# matrix.net
KiCad netlist of a schematic drawn in EAGLE
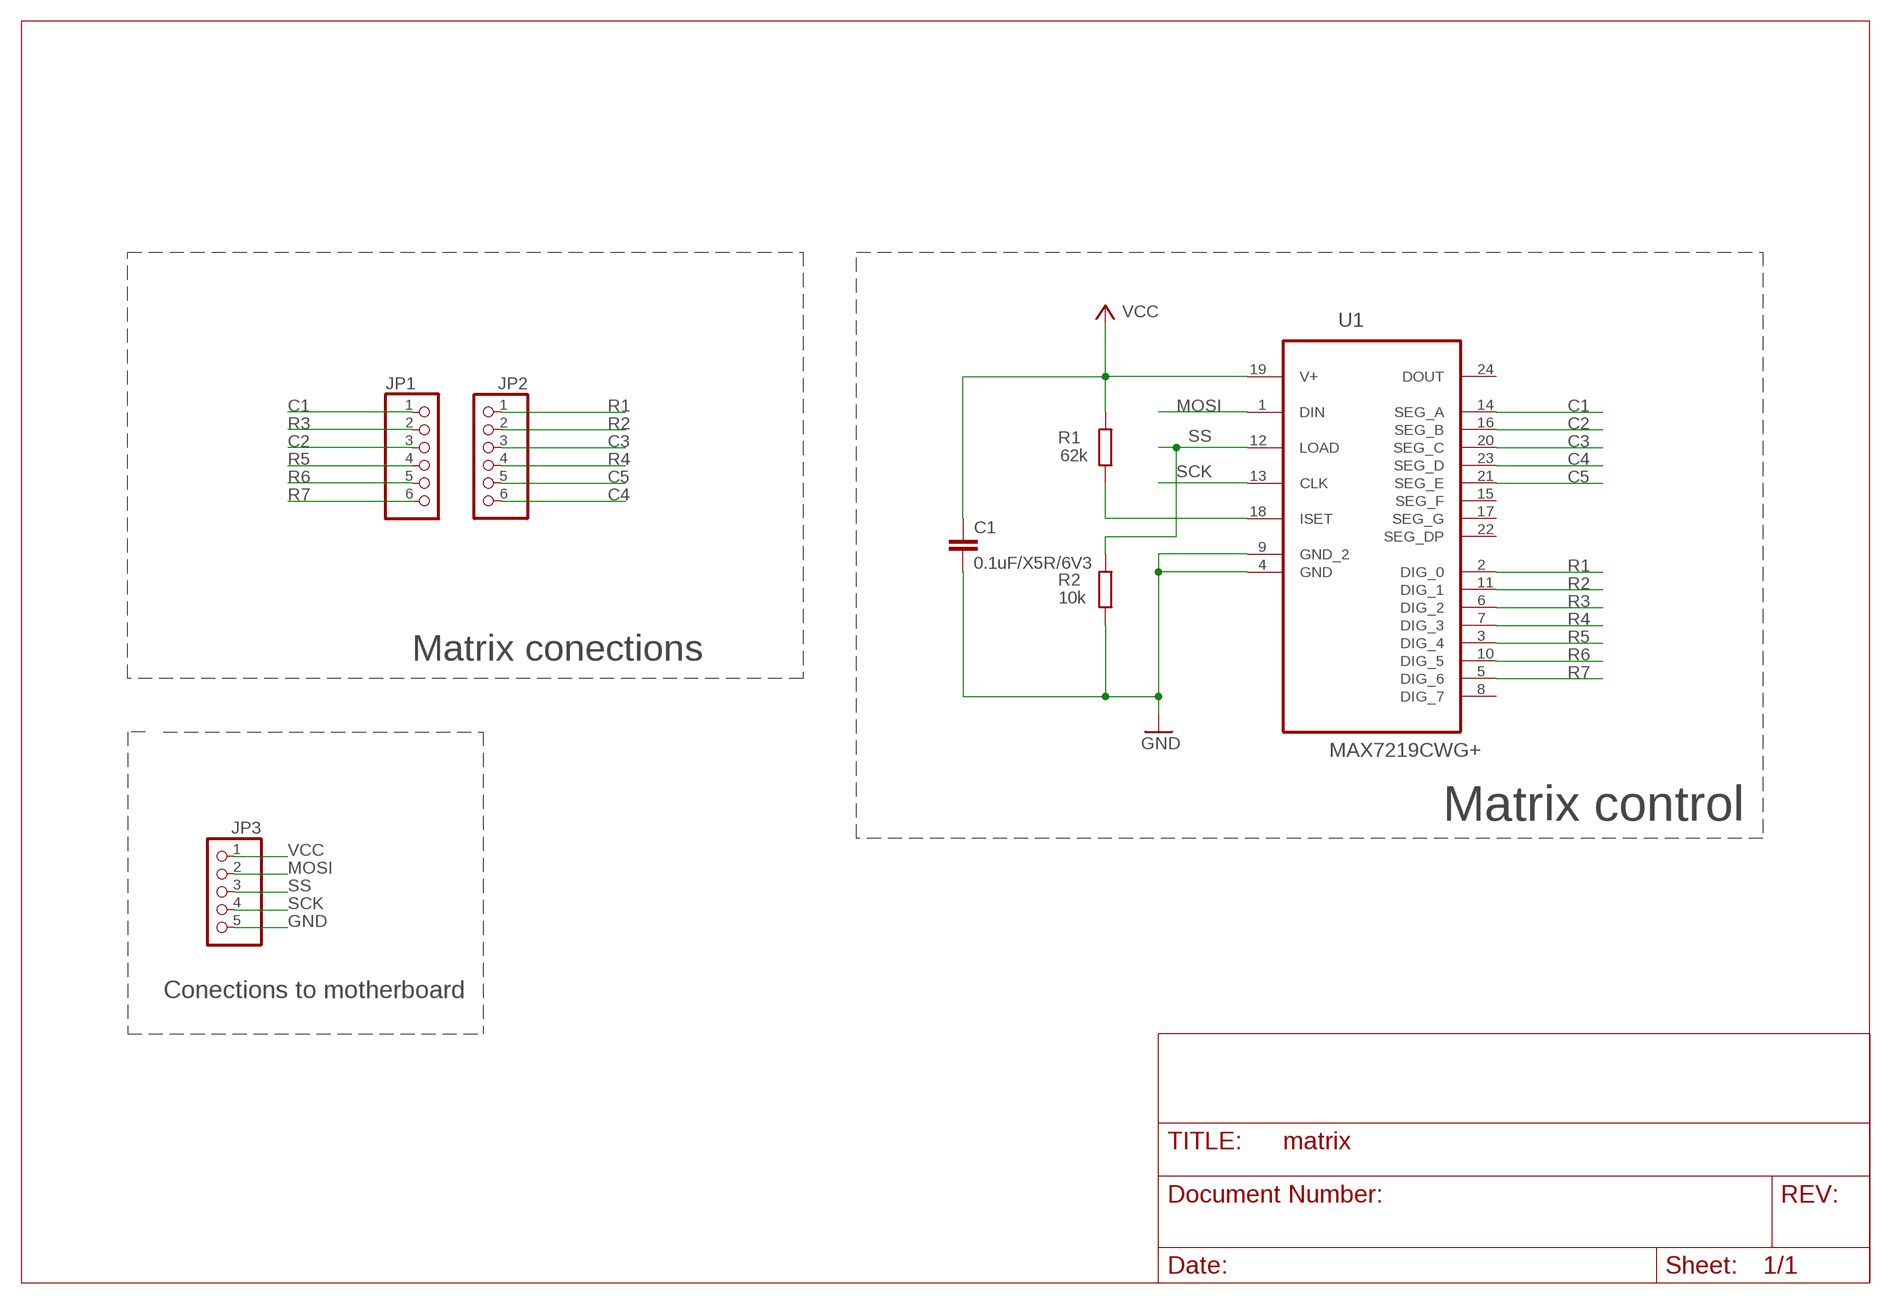
[diagram p0: schematic, sheet 1]

(export (version "E")
  (design (tool "Eeschema 10.0.6"))
  (components
    (comp (ref "C1")
      (value "0.1uF/X5R/6V3")
      (footprint "eagle-import:C1206")
      (libsource (lib "eagle-import") (part "C-EUC1206"))
    )
    (comp (ref "JP1")
      (value "PINHD-1X6")
      (footprint "eagle-import:1X06")
      (libsource (lib "eagle-import") (part "PINHD-1X6"))
    )
    (comp (ref "JP2")
      (value "PINHD-1X6")
      (footprint "eagle-import:1X06")
      (libsource (lib "eagle-import") (part "PINHD-1X6"))
    )
    (comp (ref "JP3")
      (value "PINHD-1X5")
      (footprint "eagle-import:1X05")
      (libsource (lib "eagle-import") (part "PINHD-1X5"))
    )
    (comp (ref "R1")
      (value "62k")
      (footprint "eagle-import:R0805")
      (libsource (lib "eagle-import") (part "R-EU_R0805"))
    )
    (comp (ref "R2")
      (value "10k")
      (footprint "eagle-import:R0805")
      (libsource (lib "eagle-import") (part "R-EU_R0805"))
    )
    (comp (ref "U1")
      (value "MAX7219CWG+")
      (footprint "eagle-import:SOIC127P1032X265-24N")
      (libsource (lib "eagle-import") (part "MAX7219CWG+"))
    )
  )
  (nets
    (net (code "1") (name "/C1") (class "Default")
      (node (ref "JP1") (pin "1") (pinfunction "1_1") (pintype "passive"))
      (node (ref "U1") (pin "14") (pinfunction "SEG_A_14") (pintype "output"))
    )
    (net (code "2") (name "/C2") (class "Default")
      (node (ref "JP1") (pin "3") (pinfunction "3_3") (pintype "passive"))
      (node (ref "U1") (pin "16") (pinfunction "SEG_B_16") (pintype "output"))
    )
    (net (code "3") (name "/C3") (class "Default")
      (node (ref "JP2") (pin "3") (pinfunction "3_3") (pintype "passive"))
      (node (ref "U1") (pin "20") (pinfunction "SEG_C_20") (pintype "output"))
    )
    (net (code "4") (name "/C4") (class "Default")
      (node (ref "JP2") (pin "6") (pinfunction "6_6") (pintype "passive"))
      (node (ref "U1") (pin "23") (pinfunction "SEG_D_23") (pintype "output"))
    )
    (net (code "5") (name "/C5") (class "Default")
      (node (ref "JP2") (pin "5") (pinfunction "5_5") (pintype "passive"))
      (node (ref "U1") (pin "21") (pinfunction "SEG_E_21") (pintype "output"))
    )
    (net (code "6") (name "/MOSI") (class "Default")
      (node (ref "JP3") (pin "2") (pinfunction "2_2") (pintype "passive"))
      (node (ref "U1") (pin "1") (pinfunction "DIN_1") (pintype "input"))
    )
    (net (code "7") (name "/R1") (class "Default")
      (node (ref "JP2") (pin "1") (pinfunction "1_1") (pintype "passive"))
      (node (ref "U1") (pin "2") (pinfunction "DIG_0_2") (pintype "output"))
    )
    (net (code "8") (name "/R2") (class "Default")
      (node (ref "JP2") (pin "2") (pinfunction "2_2") (pintype "passive"))
      (node (ref "U1") (pin "11") (pinfunction "DIG_1_11") (pintype "output"))
    )
    (net (code "9") (name "/R3") (class "Default")
      (node (ref "JP1") (pin "2") (pinfunction "2_2") (pintype "passive"))
      (node (ref "U1") (pin "6") (pinfunction "DIG_2_6") (pintype "output"))
    )
    (net (code "10") (name "/R4") (class "Default")
      (node (ref "JP2") (pin "4") (pinfunction "4_4") (pintype "passive"))
      (node (ref "U1") (pin "7") (pinfunction "DIG_3_7") (pintype "output"))
    )
    (net (code "11") (name "/R5") (class "Default")
      (node (ref "JP1") (pin "4") (pinfunction "4_4") (pintype "passive"))
      (node (ref "U1") (pin "3") (pinfunction "DIG_4_3") (pintype "output"))
    )
    (net (code "12") (name "/R6") (class "Default")
      (node (ref "JP1") (pin "5") (pinfunction "5_5") (pintype "passive"))
      (node (ref "U1") (pin "10") (pinfunction "DIG_5_10") (pintype "output"))
    )
    (net (code "13") (name "/R7") (class "Default")
      (node (ref "JP1") (pin "6") (pinfunction "6_6") (pintype "passive"))
      (node (ref "U1") (pin "5") (pinfunction "DIG_6_5") (pintype "output"))
    )
    (net (code "14") (name "/SCK") (class "Default")
      (node (ref "JP3") (pin "4") (pinfunction "4_4") (pintype "passive"))
      (node (ref "U1") (pin "13") (pinfunction "CLK_13") (pintype "input"))
    )
    (net (code "15") (name "/SS") (class "Default")
      (node (ref "JP3") (pin "3") (pinfunction "3_3") (pintype "passive"))
      (node (ref "R2") (pin "2") (pinfunction "2_2") (pintype "passive"))
      (node (ref "U1") (pin "12") (pinfunction "LOAD_12") (pintype "input"))
    )
    (net (code "16") (name "GND") (class "Default")
      (node (ref "C1") (pin "2") (pinfunction "2_2") (pintype "passive"))
      (node (ref "JP3") (pin "5") (pinfunction "5_5") (pintype "passive"))
      (node (ref "R2") (pin "1") (pinfunction "1_1") (pintype "passive"))
      (node (ref "U1") (pin "4") (pinfunction "GND_4") (pintype "passive"))
      (node (ref "U1") (pin "9") (pinfunction "GND_2_9") (pintype "passive"))
    )
    (net (code "17") (name "Net-(U1-ISET)") (class "Default")
      (node (ref "R1") (pin "1") (pinfunction "1_1") (pintype "passive"))
      (node (ref "U1") (pin "18") (pinfunction "ISET_18") (pintype "input"))
    )
    (net (code "18") (name "VCC") (class "Default")
      (node (ref "C1") (pin "1") (pinfunction "1_1") (pintype "passive"))
      (node (ref "JP3") (pin "1") (pinfunction "1_1") (pintype "passive"))
      (node (ref "R1") (pin "2") (pinfunction "2_2") (pintype "passive"))
      (node (ref "U1") (pin "19") (pinfunction "V+_19") (pintype "power_in"))
    )
    (net (code "19") (name "unconnected-(U1-DIG_7-Pad8)") (class "Default")
      (node (ref "U1") (pin "8") (pinfunction "DIG_7_8") (pintype "output"))
    )
    (net (code "20") (name "unconnected-(U1-DOUT-Pad24)") (class "Default")
      (node (ref "U1") (pin "24") (pinfunction "DOUT_24") (pintype "output"))
    )
    (net (code "21") (name "unconnected-(U1-SEG_DP-Pad22)") (class "Default")
      (node (ref "U1") (pin "22") (pinfunction "SEG_DP_22") (pintype "output"))
    )
    (net (code "22") (name "unconnected-(U1-SEG_F-Pad15)") (class "Default")
      (node (ref "U1") (pin "15") (pinfunction "SEG_F_15") (pintype "output"))
    )
    (net (code "23") (name "unconnected-(U1-SEG_G-Pad17)") (class "Default")
      (node (ref "U1") (pin "17") (pinfunction "SEG_G_17") (pintype "output"))
    )
  )
)
